# MGT_PWR.net
KiCad netlist of a schematic drawn in Altium Designer
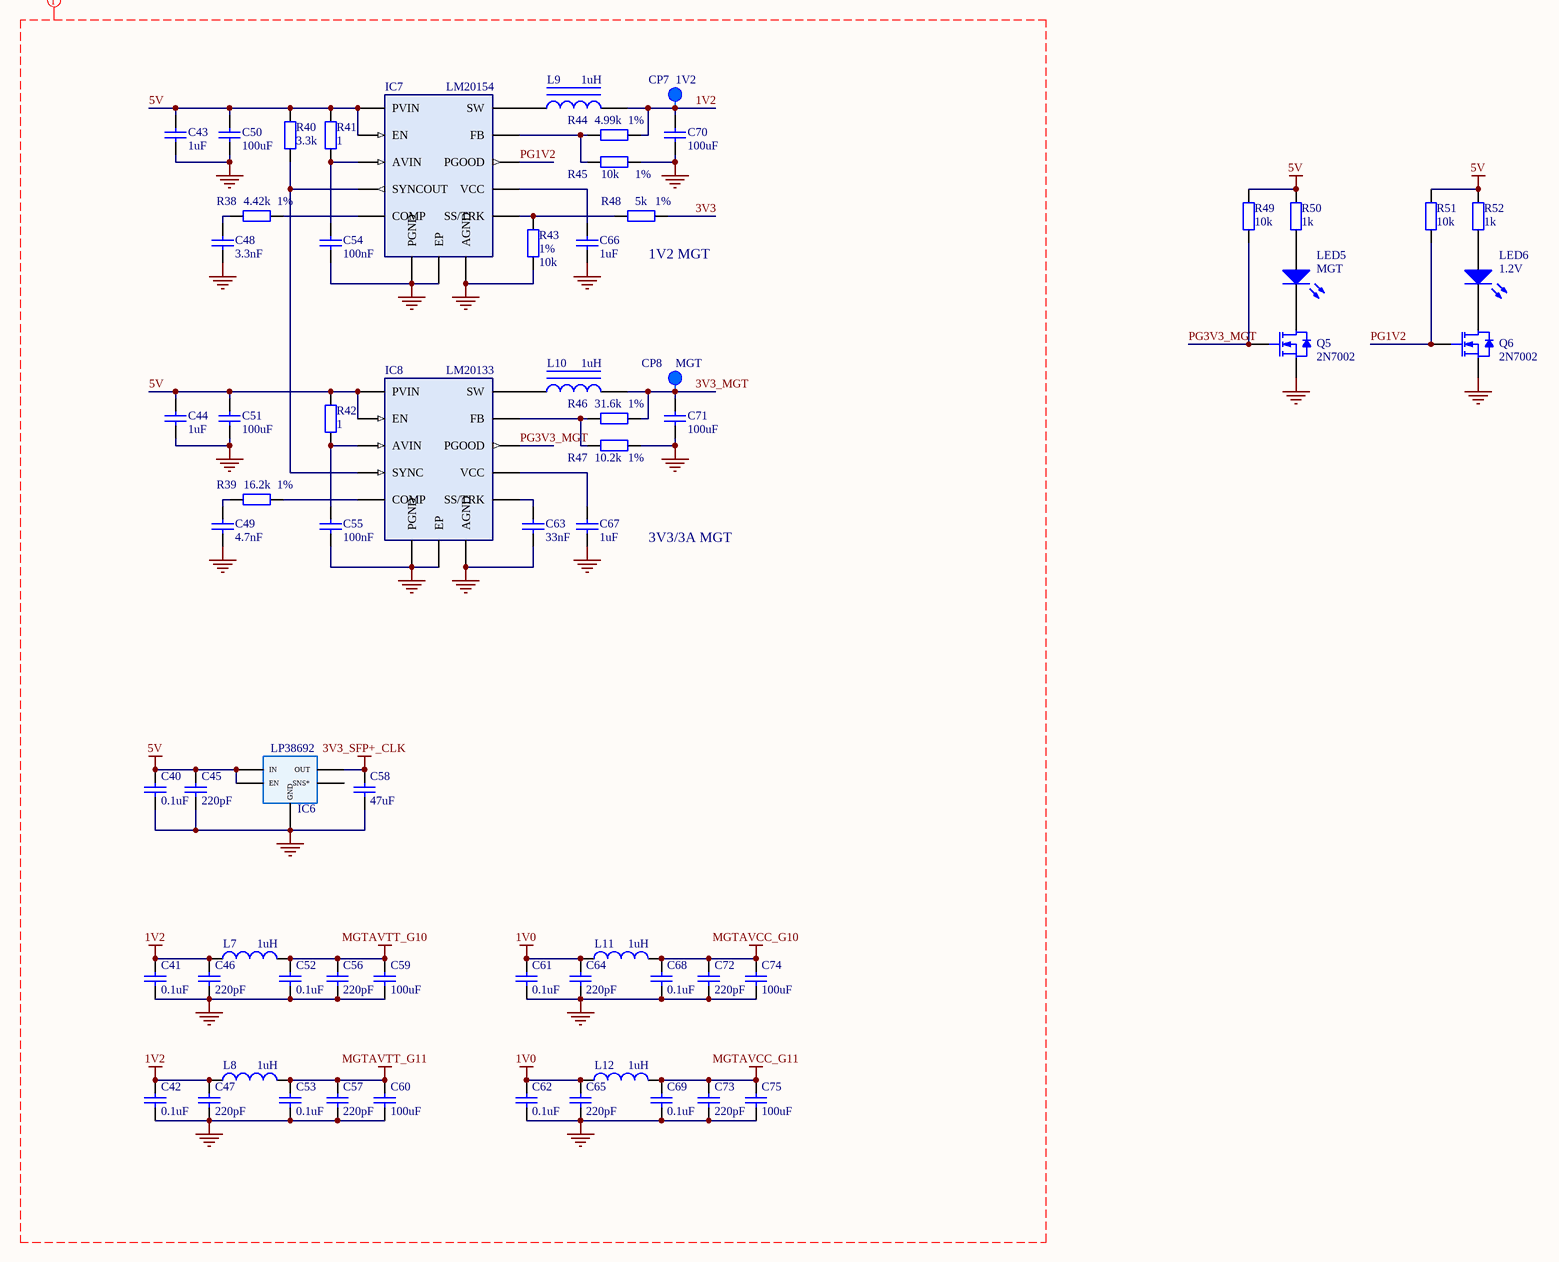
[diagram p0: MGT_PWR.SchDoc]

(export (version "E")
  (design (tool "Eeschema 10.0.6"))
  (components
    (comp (ref "C40")
      (value "0.1uF")
      (footprint "C0603")
      (description "Cer Cap Small")
      (fields (field (name "MANUFACTURER") "Murata") (field (name "VOLTAGE") "16V"))
      (libsource (lib "USRP2_Clone") (part "Cer Cap"))
    )
    (comp (ref "C41")
      (value "0.1uF")
      (footprint "C0603")
      (description "Cer Cap Small")
      (fields (field (name "MANUFACTURER") "Murata") (field (name "VOLTAGE") "16V"))
      (libsource (lib "USRP2_Clone") (part "Cer Cap"))
    )
    (comp (ref "C42")
      (value "0.1uF")
      (footprint "C0603")
      (description "Cer Cap Small")
      (fields (field (name "MANUFACTURER") "Murata") (field (name "VOLTAGE") "16V"))
      (libsource (lib "USRP2_Clone") (part "Cer Cap"))
    )
    (comp (ref "C43")
      (value "1uF")
      (footprint "C0805")
      (description "Cer Cap Small")
      (fields (field (name "MANUFACTURER") "Murata") (field (name "VOLTAGE") "16V"))
      (libsource (lib "USRP2_Clone") (part "Cer Cap"))
    )
    (comp (ref "C44")
      (value "1uF")
      (footprint "C0805")
      (description "Cer Cap Small")
      (fields (field (name "MANUFACTURER") "Murata") (field (name "VOLTAGE") "16V"))
      (libsource (lib "USRP2_Clone") (part "Cer Cap"))
    )
    (comp (ref "C45")
      (value "220pF")
      (footprint "C0603")
      (description "Cer Cap Small")
      (fields (field (name "MANUFACTURER") "Murata") (field (name "VOLTAGE") "16V"))
      (libsource (lib "USRP2_Clone") (part "Cer Cap"))
    )
    (comp (ref "C46")
      (value "220pF")
      (footprint "C0603")
      (description "Cer Cap Small")
      (fields (field (name "MANUFACTURER") "Murata") (field (name "VOLTAGE") "16V"))
      (libsource (lib "USRP2_Clone") (part "Cer Cap"))
    )
    (comp (ref "C47")
      (value "220pF")
      (footprint "C0603")
      (description "Cer Cap Small")
      (fields (field (name "MANUFACTURER") "Murata") (field (name "VOLTAGE") "16V"))
      (libsource (lib "USRP2_Clone") (part "Cer Cap"))
    )
    (comp (ref "C48")
      (value "3.3nF")
      (footprint "C0603")
      (description "Cer Cap Small")
      (fields (field (name "MANUFACTURER") "Murata") (field (name "VOLTAGE") "25V"))
      (libsource (lib "") (part "Cer Cap_1"))
    )
    (comp (ref "C49")
      (value "4.7nF")
      (footprint "C0603")
      (description "Cer Cap Small")
      (fields (field (name "MANUFACTURER") "Murata") (field (name "VOLTAGE") "25V"))
      (libsource (lib "") (part "Cer Cap_1"))
    )
    (comp (ref "C50")
      (value "100uF")
      (footprint "C1210")
      (description "Cer Cap Large")
      (fields (field (name "MANUFACTURER") "Murata") (field (name "TOLERANCE") "20%"))
      (libsource (lib "") (part "Cap uF_1"))
    )
    (comp (ref "C51")
      (value "100uF")
      (footprint "C1210")
      (description "Cer Cap Large")
      (fields (field (name "MANUFACTURER") "Murata") (field (name "TOLERANCE") "20%"))
      (libsource (lib "") (part "Cap uF_1"))
    )
    (comp (ref "C52")
      (value "0.1uF")
      (footprint "C0603")
      (description "Cer Cap Small")
      (fields (field (name "MANUFACTURER") "Murata") (field (name "VOLTAGE") "16V"))
      (libsource (lib "USRP2_Clone") (part "Cer Cap"))
    )
    (comp (ref "C53")
      (value "0.1uF")
      (footprint "C0603")
      (description "Cer Cap Small")
      (fields (field (name "MANUFACTURER") "Murata") (field (name "VOLTAGE") "16V"))
      (libsource (lib "USRP2_Clone") (part "Cer Cap"))
    )
    (comp (ref "C54")
      (value "100nF")
      (footprint "C0603")
      (description "Cer Cap Small")
      (fields (field (name "MANUFACTURER") "Murata") (field (name "VOLTAGE") "16V"))
      (libsource (lib "") (part "Cer Cap_1"))
    )
    (comp (ref "C55")
      (value "100nF")
      (footprint "C0603")
      (description "Cer Cap Small")
      (fields (field (name "MANUFACTURER") "Murata") (field (name "VOLTAGE") "16V"))
      (libsource (lib "") (part "Cer Cap_1"))
    )
    (comp (ref "C56")
      (value "220pF")
      (footprint "C0603")
      (description "Cer Cap Small")
      (fields (field (name "MANUFACTURER") "Murata") (field (name "VOLTAGE") "16V"))
      (libsource (lib "USRP2_Clone") (part "Cer Cap"))
    )
    (comp (ref "C57")
      (value "220pF")
      (footprint "C0603")
      (description "Cer Cap Small")
      (fields (field (name "MANUFACTURER") "Murata") (field (name "VOLTAGE") "16V"))
      (libsource (lib "USRP2_Clone") (part "Cer Cap"))
    )
    (comp (ref "C58")
      (value "47uF")
      (footprint "C1210")
      (description "Cer Cap Large")
      (fields (field (name "MANUFACTURER") "Murata") (field (name "TOLERANCE") "20%"))
      (libsource (lib "") (part "Cap uF_1"))
    )
    (comp (ref "C59")
      (value "100uF")
      (footprint "C1210")
      (description "Cer Cap Large")
      (fields (field (name "MANUFACTURER") "Murata") (field (name "TOLERANCE") "20%"))
      (libsource (lib "") (part "Cap uF_1"))
    )
    (comp (ref "C60")
      (value "100uF")
      (footprint "C1210")
      (description "Cer Cap Large")
      (fields (field (name "MANUFACTURER") "Murata") (field (name "TOLERANCE") "20%"))
      (libsource (lib "") (part "Cap uF_1"))
    )
    (comp (ref "C61")
      (value "0.1uF")
      (footprint "C0603")
      (description "Cer Cap Small")
      (fields (field (name "MANUFACTURER") "Murata") (field (name "VOLTAGE") "16V"))
      (libsource (lib "") (part "Cer Cap_1"))
    )
    (comp (ref "C62")
      (value "0.1uF")
      (footprint "C0603")
      (description "Cer Cap Small")
      (fields (field (name "MANUFACTURER") "Murata") (field (name "VOLTAGE") "16V"))
      (libsource (lib "") (part "Cer Cap_1"))
    )
    (comp (ref "C63")
      (value "33nF")
      (footprint "C0603")
      (description "Cer Cap Small")
      (fields (field (name "MANUFACTURER") "Murata") (field (name "VOLTAGE") "25V"))
      (libsource (lib "USRP2_Clone") (part "Cer Cap"))
    )
    (comp (ref "C64")
      (value "220pF")
      (footprint "C0603")
      (description "Cer Cap Small")
      (fields (field (name "MANUFACTURER") "Murata") (field (name "VOLTAGE") "16V"))
      (libsource (lib "") (part "Cer Cap_1"))
    )
    (comp (ref "C65")
      (value "220pF")
      (footprint "C0603")
      (description "Cer Cap Small")
      (fields (field (name "MANUFACTURER") "Murata") (field (name "VOLTAGE") "16V"))
      (libsource (lib "USRP2_Clone") (part "Cer Cap"))
    )
    (comp (ref "C66")
      (value "1uF")
      (footprint "C0603")
      (description "Cer Cap Small")
      (fields (field (name "MANUFACTURER") "Murata") (field (name "VOLTAGE") "6.3V"))
      (libsource (lib "USRP2_Clone") (part "Cer Cap"))
    )
    (comp (ref "C67")
      (value "1uF")
      (footprint "C0603")
      (description "Cer Cap Small")
      (fields (field (name "MANUFACTURER") "Murata") (field (name "VOLTAGE") "6.3V"))
      (libsource (lib "") (part "Cer Cap_1"))
    )
    (comp (ref "C68")
      (value "0.1uF")
      (footprint "C0603")
      (description "Cer Cap Small")
      (fields (field (name "MANUFACTURER") "Murata") (field (name "VOLTAGE") "16V"))
      (libsource (lib "USRP2_Clone") (part "Cer Cap"))
    )
    (comp (ref "C69")
      (value "0.1uF")
      (footprint "C0603")
      (description "Cer Cap Small")
      (fields (field (name "MANUFACTURER") "Murata") (field (name "VOLTAGE") "16V"))
      (libsource (lib "USRP2_Clone") (part "Cer Cap"))
    )
    (comp (ref "C70")
      (value "100uF")
      (footprint "C1210")
      (description "Cer Cap Large")
      (fields (field (name "MANUFACTURER") "Murata") (field (name "TOLERANCE") "20%"))
      (libsource (lib "USRP2_Clone") (part "Cap uF"))
    )
    (comp (ref "C71")
      (value "100uF")
      (footprint "C1210")
      (description "Cer Cap Large")
      (fields (field (name "MANUFACTURER") "Murata") (field (name "TOLERANCE") "20%"))
      (libsource (lib "USRP2_Clone") (part "Cap uF"))
    )
    (comp (ref "C72")
      (value "220pF")
      (footprint "C0603")
      (description "Cer Cap Small")
      (fields (field (name "MANUFACTURER") "Murata") (field (name "VOLTAGE") "16V"))
      (libsource (lib "USRP2_Clone") (part "Cer Cap"))
    )
    (comp (ref "C73")
      (value "220pF")
      (footprint "C0603")
      (description "Cer Cap Small")
      (fields (field (name "MANUFACTURER") "Murata") (field (name "VOLTAGE") "16V"))
      (libsource (lib "USRP2_Clone") (part "Cer Cap"))
    )
    (comp (ref "C74")
      (value "100uF")
      (footprint "C1210")
      (description "Cer Cap Large")
      (fields (field (name "MANUFACTURER") "Murata") (field (name "TOLERANCE") "20%"))
      (libsource (lib "") (part "Cap uF_1"))
    )
    (comp (ref "C75")
      (value "100uF")
      (footprint "C1210")
      (description "Cer Cap Large")
      (fields (field (name "MANUFACTURER") "Murata") (field (name "TOLERANCE") "20%"))
      (libsource (lib "") (part "Cap uF_1"))
    )
    (comp (ref "CP7")
      (value "1V2")
      (footprint "Control Point")
      (description "Control Point")
      (libsource (lib "USRP2_Clone") (part "Control Point"))
    )
    (comp (ref "CP8")
      (value "MGT")
      (footprint "Control Point")
      (description "Control Point")
      (libsource (lib "USRP2_Clone") (part "Control Point"))
    )
    (comp (ref "IC6")
      (value "LP38692")
      (footprint "SOT-223-5")
      (description "Linear Regulator")
      (libsource (lib "USRP2_Clone") (part "LP38692"))
    )
    (comp (ref "IC7")
      (value "LM20154")
      (footprint "LM201xx")
      (description "Synchrous Buck Regulator")
      (libsource (lib "USRP2_Clone") (part "LM20154"))
    )
    (comp (ref "IC8")
      (value "LM20133")
      (footprint "LM201xx")
      (description "Synchronous Buck Regulator")
      (libsource (lib "USRP2_Clone") (part "LM20133"))
    )
    (comp (ref "L7")
      (value "1uH")
      (footprint "L1210_Murata LQH")
      (description "Inductor_Power_Lines")
      (fields (field (name "TOLERANCE") "5%") (field (name "MANUFACTURER") "Murata"))
      (libsource (lib "USRP2_Clone") (part "Inductor_LF"))
    )
    (comp (ref "L8")
      (value "1uH")
      (footprint "L1210_Murata LQH")
      (description "Inductor_Power_Lines")
      (fields (field (name "TOLERANCE") "5%") (field (name "MANUFACTURER") "Murata"))
      (libsource (lib "USRP2_Clone") (part "Inductor_LF"))
    )
    (comp (ref "L9")
      (value "1uH")
      (footprint "Coilcraft MSS1038")
      (description "Magnetic-Core Inductor")
      (fields (field (name "TOLERANCE") "±30%") (field (name "MANUFACTURER") "Coilcraft"))
      (libsource (lib "USRP2_Clone") (part "Inductor Power"))
    )
    (comp (ref "L10")
      (value "1uH")
      (footprint "Coilcraft MSS1038")
      (description "Magnetic-Core Inductor")
      (fields (field (name "TOLERANCE") "±30%") (field (name "MANUFACTURER") "Coilcraft"))
      (libsource (lib "USRP2_Clone") (part "Inductor Power"))
    )
    (comp (ref "L11")
      (value "1uH")
      (footprint "L1210_Murata LQH")
      (description "Inductor_Power_Lines")
      (fields (field (name "TOLERANCE") "5%") (field (name "MANUFACTURER") "Murata"))
      (libsource (lib "USRP2_Clone") (part "Inductor_LF"))
    )
    (comp (ref "L12")
      (value "1uH")
      (footprint "L1210_Murata LQH")
      (description "Inductor_Power_Lines")
      (fields (field (name "TOLERANCE") "5%") (field (name "MANUFACTURER") "Murata"))
      (libsource (lib "USRP2_Clone") (part "Inductor_LF"))
    )
    (comp (ref "LED5")
      (value "MGT")
      (footprint "LED_0402_Blue")
      (description "Typical RED, GREEN, YELLOW, AMBER GaAs LED")
      (fields (field (name "MANUFACTURER") "Kingbright"))
      (libsource (lib "USRP2_Clone") (part "LED"))
    )
    (comp (ref "LED6")
      (value "1.2V")
      (footprint "LED_0402_Blue")
      (description "Typical RED, GREEN, YELLOW, AMBER GaAs LED")
      (fields (field (name "MANUFACTURER") "Kingbright"))
      (libsource (lib "USRP2_Clone") (part "LED"))
    )
    (comp (ref "Q5")
      (value "2N7002")
      (footprint "SOT-23")
      (description "N-Channel MOSFET 2N7002")
      (fields (field (name "VOLTAGE") "60V"))
      (libsource (lib "USRP2_Clone") (part "2N7002"))
    )
    (comp (ref "Q6")
      (value "2N7002")
      (footprint "SOT-23")
      (description "N-Channel MOSFET 2N7002")
      (fields (field (name "VOLTAGE") "60V"))
      (libsource (lib "USRP2_Clone") (part "2N7002"))
    )
    (comp (ref "R38")
      (value "4.42k")
      (footprint "R0603")
      (description "Resistor")
      (fields
        (field (name "TOLERANCE") "1%")
        (field (name "POWER") "0.062 Wt")
        (field (name "Comment") "Res")
      )
      (libsource (lib "") (part "Res_3"))
    )
    (comp (ref "R39")
      (value "16.2k")
      (footprint "R0603")
      (description "Resistor")
      (fields
        (field (name "TOLERANCE") "1%")
        (field (name "POWER") "0.062 Wt")
        (field (name "Comment") "Res")
      )
      (libsource (lib "") (part "Res_2"))
    )
    (comp (ref "R40")
      (value "3.3k")
      (footprint "R0603")
      (description "Resistor")
      (fields (field (name "TOLERANCE") "5%") (field (name "POWER") "0.062 Wt"))
      (libsource (lib "") (part "Res_1"))
    )
    (comp (ref "R41")
      (value "1")
      (footprint "R0603")
      (description "Resistor")
      (fields (field (name "TOLERANCE") "5%") (field (name "POWER") "0.062 Wt"))
      (libsource (lib "") (part "Res_5"))
    )
    (comp (ref "R42")
      (value "1")
      (footprint "R0603")
      (description "Resistor")
      (fields (field (name "TOLERANCE") "5%") (field (name "POWER") "0.062 Wt"))
      (libsource (lib "USRP2_Clone") (part "Res"))
    )
    (comp (ref "R43")
      (value "10k")
      (footprint "R0603")
      (description "Resistor")
      (fields
        (field (name "TOLERANCE") "1%")
        (field (name "POWER") "0.062 Wt")
        (field (name "Comment") "Res")
      )
      (libsource (lib "") (part "Res_4"))
    )
    (comp (ref "R44")
      (value "4.99k")
      (footprint "R0603")
      (description "Resistor")
      (fields
        (field (name "TOLERANCE") "1%")
        (field (name "POWER") "0.062 Wt")
        (field (name "Comment") "Res")
      )
      (libsource (lib "") (part "Res_2"))
    )
    (comp (ref "R45")
      (value "10k")
      (footprint "R0603")
      (description "Resistor")
      (fields
        (field (name "TOLERANCE") "1%")
        (field (name "POWER") "0.062 Wt")
        (field (name "Comment") "Res")
      )
      (libsource (lib "") (part "Res_3"))
    )
    (comp (ref "R46")
      (value "31.6k")
      (footprint "R0603")
      (description "Resistor")
      (fields
        (field (name "TOLERANCE") "1%")
        (field (name "POWER") "0.062 Wt")
        (field (name "Comment") "Res")
      )
      (libsource (lib "") (part "Res_2"))
    )
    (comp (ref "R47")
      (value "10.2k")
      (footprint "R0603")
      (description "Resistor")
      (fields
        (field (name "TOLERANCE") "1%")
        (field (name "POWER") "0.062 Wt")
        (field (name "Comment") "Res")
      )
      (libsource (lib "") (part "Res_3"))
    )
    (comp (ref "R48")
      (value "5k")
      (footprint "R0603")
      (description "Resistor")
      (fields
        (field (name "TOLERANCE") "1%")
        (field (name "POWER") "0.062 Wt")
        (field (name "Comment") "Res")
      )
      (libsource (lib "") (part "Res_2"))
    )
    (comp (ref "R49")
      (value "10k")
      (footprint "R0402")
      (description "Resistor")
      (fields (field (name "TOLERANCE") "5%") (field (name "POWER") "0.062 Wt"))
      (libsource (lib "USRP2_Clone") (part "Res"))
    )
    (comp (ref "R50")
      (value "1k")
      (footprint "R0402")
      (description "Resistor")
      (fields (field (name "TOLERANCE") "5%") (field (name "POWER") "0.062 Wt"))
      (libsource (lib "USRP2_Clone") (part "Res"))
    )
    (comp (ref "R51")
      (value "10k")
      (footprint "R0402")
      (description "Resistor")
      (fields (field (name "TOLERANCE") "5%") (field (name "POWER") "0.062 Wt"))
      (libsource (lib "USRP2_Clone") (part "Res"))
    )
    (comp (ref "R52")
      (value "1k")
      (footprint "R0402")
      (description "Resistor")
      (fields (field (name "TOLERANCE") "5%") (field (name "POWER") "0.062 Wt"))
      (libsource (lib "USRP2_Clone") (part "Res"))
    )
  )
  (nets
    (net (code "1") (name "/3V3") (class "Default")
      (node (ref "R48") (pin "1") (pinfunction "1_1") (pintype "passive"))
    )
    (net (code "2") (name "/3V3_MGT") (class "Default")
      (node (ref "C71") (pin "2") (pinfunction "2_2") (pintype "passive"))
      (node (ref "CP8") (pin "1") (pinfunction "1_1") (pintype "passive"))
      (node (ref "L10") (pin "2") (pinfunction "2_2") (pintype "passive"))
      (node (ref "R46") (pin "1") (pinfunction "1_1") (pintype "passive"))
    )
    (net (code "3") (name "/PG1V2") (class "Default")
      (node (ref "IC7") (pin "3") (pinfunction "PGOOD_3") (pintype "output"))
      (node (ref "Q6") (pin "1") (pinfunction "G_1") (pintype "passive"))
      (node (ref "R51") (pin "1") (pinfunction "1_1") (pintype "passive"))
    )
    (net (code "4") (name "/PG3V3_MGT") (class "Default")
      (node (ref "IC8") (pin "3") (pinfunction "PGOOD_3") (pintype "output"))
      (node (ref "Q5") (pin "1") (pinfunction "G_1") (pintype "passive"))
      (node (ref "R49") (pin "1") (pinfunction "1_1") (pintype "passive"))
    )
    (net (code "5") (name "1V0") (class "Default")
      (node (ref "C61") (pin "2") (pinfunction "2_2") (pintype "passive"))
      (node (ref "C62") (pin "2") (pinfunction "2_2") (pintype "passive"))
      (node (ref "C64") (pin "2") (pinfunction "2_2") (pintype "passive"))
      (node (ref "C65") (pin "1") (pinfunction "1_1") (pintype "passive"))
      (node (ref "L11") (pin "2") (pinfunction "2_2") (pintype "passive"))
      (node (ref "L12") (pin "2") (pinfunction "2_2") (pintype "passive"))
    )
    (net (code "6") (name "1V2") (class "Default")
      (node (ref "C41") (pin "1") (pinfunction "1_1") (pintype "passive"))
      (node (ref "C42") (pin "1") (pinfunction "1_1") (pintype "passive"))
      (node (ref "C46") (pin "1") (pinfunction "1_1") (pintype "passive"))
      (node (ref "C47") (pin "1") (pinfunction "1_1") (pintype "passive"))
      (node (ref "C70") (pin "2") (pinfunction "2_2") (pintype "passive"))
      (node (ref "CP7") (pin "1") (pinfunction "1_1") (pintype "passive"))
      (node (ref "L7") (pin "2") (pinfunction "2_2") (pintype "passive"))
      (node (ref "L8") (pin "2") (pinfunction "2_2") (pintype "passive"))
      (node (ref "L9") (pin "2") (pinfunction "2_2") (pintype "passive"))
      (node (ref "R44") (pin "1") (pinfunction "1_1") (pintype "passive"))
    )
    (net (code "7") (name "3V3_SFP+_CLK") (class "Default")
      (node (ref "C58") (pin "1") (pinfunction "1_1") (pintype "passive"))
      (node (ref "IC6") (pin "3") (pinfunction "OUT_3") (pintype "passive"))
    )
    (net (code "8") (name "5V") (class "Default")
      (node (ref "C40") (pin "1") (pinfunction "1_1") (pintype "passive"))
      (node (ref "C43") (pin "1") (pinfunction "1_1") (pintype "passive"))
      (node (ref "C44") (pin "1") (pinfunction "1_1") (pintype "passive"))
      (node (ref "C45") (pin "1") (pinfunction "1_1") (pintype "passive"))
      (node (ref "C50") (pin "1") (pinfunction "1_1") (pintype "passive"))
      (node (ref "C51") (pin "1") (pinfunction "1_1") (pintype "passive"))
      (node (ref "IC6") (pin "1") (pinfunction "EN_1") (pintype "passive"))
      (node (ref "IC6") (pin "4") (pinfunction "IN_4") (pintype "passive"))
      (node (ref "IC7") (pin "12") (pinfunction "EN_12") (pintype "input"))
      (node (ref "IC7") (pin "6") (pinfunction "PVIN_6") (pintype "passive"))
      (node (ref "IC8") (pin "12") (pinfunction "EN_12") (pintype "input"))
      (node (ref "IC8") (pin "6") (pinfunction "PVIN_6") (pintype "passive"))
      (node (ref "R40") (pin "2") (pinfunction "2_2") (pintype "passive"))
      (node (ref "R41") (pin "1") (pinfunction "1_1") (pintype "passive"))
      (node (ref "R42") (pin "2") (pinfunction "2_2") (pintype "passive"))
      (node (ref "R49") (pin "2") (pinfunction "2_2") (pintype "passive"))
      (node (ref "R50") (pin "2") (pinfunction "2_2") (pintype "passive"))
      (node (ref "R51") (pin "2") (pinfunction "2_2") (pintype "passive"))
      (node (ref "R52") (pin "2") (pinfunction "2_2") (pintype "passive"))
    )
    (net (code "9") (name "GND") (class "Default")
      (node (ref "C40") (pin "2") (pinfunction "2_2") (pintype "passive"))
      (node (ref "C41") (pin "2") (pinfunction "2_2") (pintype "passive"))
      (node (ref "C42") (pin "2") (pinfunction "2_2") (pintype "passive"))
      (node (ref "C43") (pin "2") (pinfunction "2_2") (pintype "passive"))
      (node (ref "C44") (pin "2") (pinfunction "2_2") (pintype "passive"))
      (node (ref "C45") (pin "2") (pinfunction "2_2") (pintype "passive"))
      (node (ref "C46") (pin "2") (pinfunction "2_2") (pintype "passive"))
      (node (ref "C47") (pin "2") (pinfunction "2_2") (pintype "passive"))
      (node (ref "C48") (pin "1") (pinfunction "1_1") (pintype "passive"))
      (node (ref "C49") (pin "1") (pinfunction "1_1") (pintype "passive"))
      (node (ref "C50") (pin "2") (pinfunction "2_2") (pintype "passive"))
      (node (ref "C51") (pin "2") (pinfunction "2_2") (pintype "passive"))
      (node (ref "C52") (pin "2") (pinfunction "2_2") (pintype "passive"))
      (node (ref "C53") (pin "2") (pinfunction "2_2") (pintype "passive"))
      (node (ref "C54") (pin "2") (pinfunction "2_2") (pintype "passive"))
      (node (ref "C55") (pin "2") (pinfunction "2_2") (pintype "passive"))
      (node (ref "C56") (pin "2") (pinfunction "2_2") (pintype "passive"))
      (node (ref "C57") (pin "2") (pinfunction "2_2") (pintype "passive"))
      (node (ref "C58") (pin "2") (pinfunction "2_2") (pintype "passive"))
      (node (ref "C59") (pin "2") (pinfunction "2_2") (pintype "passive"))
      (node (ref "C60") (pin "2") (pinfunction "2_2") (pintype "passive"))
      (node (ref "C61") (pin "1") (pinfunction "1_1") (pintype "passive"))
      (node (ref "C62") (pin "1") (pinfunction "1_1") (pintype "passive"))
      (node (ref "C63") (pin "2") (pinfunction "2_2") (pintype "passive"))
      (node (ref "C64") (pin "1") (pinfunction "1_1") (pintype "passive"))
      (node (ref "C65") (pin "2") (pinfunction "2_2") (pintype "passive"))
      (node (ref "C66") (pin "2") (pinfunction "2_2") (pintype "passive"))
      (node (ref "C67") (pin "1") (pinfunction "1_1") (pintype "passive"))
      (node (ref "C68") (pin "2") (pinfunction "2_2") (pintype "passive"))
      (node (ref "C69") (pin "2") (pinfunction "2_2") (pintype "passive"))
      (node (ref "C70") (pin "1") (pinfunction "1_1") (pintype "passive"))
      (node (ref "C71") (pin "1") (pinfunction "1_1") (pintype "passive"))
      (node (ref "C72") (pin "2") (pinfunction "2_2") (pintype "passive"))
      (node (ref "C73") (pin "2") (pinfunction "2_2") (pintype "passive"))
      (node (ref "C74") (pin "2") (pinfunction "2_2") (pintype "passive"))
      (node (ref "C75") (pin "2") (pinfunction "2_2") (pintype "passive"))
      (node (ref "IC6") (pin "5") (pinfunction "GND_5") (pintype "passive"))
      (node (ref "IC7") (pin "10") (pinfunction "PGND_10") (pintype "passive"))
      (node (ref "IC7") (pin "15") (pinfunction "AGND_15") (pintype "passive"))
      (node (ref "IC7") (pin "17") (pinfunction "EP_17") (pintype "passive"))
      (node (ref "IC8") (pin "10") (pinfunction "PGND_10") (pintype "passive"))
      (node (ref "IC8") (pin "15") (pinfunction "AGND_15") (pintype "passive"))
      (node (ref "IC8") (pin "17") (pinfunction "EP_17") (pintype "passive"))
      (node (ref "Q5") (pin "2") (pinfunction "S_2") (pintype "passive"))
      (node (ref "Q6") (pin "2") (pinfunction "S_2") (pintype "passive"))
      (node (ref "R43") (pin "2") (pinfunction "2_2") (pintype "passive"))
      (node (ref "R45") (pin "2") (pinfunction "2_2") (pintype "passive"))
      (node (ref "R47") (pin "2") (pinfunction "2_2") (pintype "passive"))
    )
    (net (code "10") (name "MGTAVCC_G10") (class "Default")
      (node (ref "C68") (pin "1") (pinfunction "1_1") (pintype "passive"))
      (node (ref "C72") (pin "1") (pinfunction "1_1") (pintype "passive"))
      (node (ref "C74") (pin "1") (pinfunction "1_1") (pintype "passive"))
      (node (ref "L11") (pin "1") (pinfunction "1_1") (pintype "passive"))
    )
    (net (code "11") (name "MGTAVCC_G11") (class "Default")
      (node (ref "C69") (pin "1") (pinfunction "1_1") (pintype "passive"))
      (node (ref "C73") (pin "1") (pinfunction "1_1") (pintype "passive"))
      (node (ref "C75") (pin "1") (pinfunction "1_1") (pintype "passive"))
      (node (ref "L12") (pin "1") (pinfunction "1_1") (pintype "passive"))
    )
    (net (code "12") (name "MGTAVTT_G10") (class "Default")
      (node (ref "C52") (pin "1") (pinfunction "1_1") (pintype "passive"))
      (node (ref "C56") (pin "1") (pinfunction "1_1") (pintype "passive"))
      (node (ref "C59") (pin "1") (pinfunction "1_1") (pintype "passive"))
      (node (ref "L7") (pin "1") (pinfunction "1_1") (pintype "passive"))
    )
    (net (code "13") (name "MGTAVTT_G11") (class "Default")
      (node (ref "C53") (pin "1") (pinfunction "1_1") (pintype "passive"))
      (node (ref "C57") (pin "1") (pinfunction "1_1") (pintype "passive"))
      (node (ref "C60") (pin "1") (pinfunction "1_1") (pintype "passive"))
      (node (ref "L8") (pin "1") (pinfunction "1_1") (pintype "passive"))
    )
    (net (code "14") (name "Net-(C48-Pad2)") (class "Default")
      (node (ref "C48") (pin "2") (pinfunction "2_2") (pintype "passive"))
      (node (ref "R38") (pin "1") (pinfunction "1_1") (pintype "passive"))
    )
    (net (code "15") (name "Net-(C49-Pad2)") (class "Default")
      (node (ref "C49") (pin "2") (pinfunction "2_2") (pintype "passive"))
      (node (ref "R39") (pin "2") (pinfunction "2_2") (pintype "passive"))
    )
    (net (code "16") (name "Net-(IC7-AVIN)") (class "Default")
      (node (ref "C54") (pin "1") (pinfunction "1_1") (pintype "passive"))
      (node (ref "IC7") (pin "14") (pinfunction "AVIN_14") (pintype "input"))
      (node (ref "R41") (pin "2") (pinfunction "2_2") (pintype "passive"))
    )
    (net (code "17") (name "Net-(IC7-COMP)") (class "Default")
      (node (ref "IC7") (pin "4") (pinfunction "COMP_4") (pintype "passive"))
      (node (ref "R38") (pin "2") (pinfunction "2_2") (pintype "passive"))
    )
    (net (code "18") (name "Net-(IC7-FB)") (class "Default")
      (node (ref "IC7") (pin "2") (pinfunction "FB_2") (pintype "passive"))
      (node (ref "R44") (pin "2") (pinfunction "2_2") (pintype "passive"))
      (node (ref "R45") (pin "1") (pinfunction "1_1") (pintype "passive"))
    )
    (net (code "19") (name "Net-(IC7-SS{slash}TRK)") (class "Default")
      (node (ref "IC7") (pin "1") (pinfunction "SS/TRK_1") (pintype "passive"))
      (node (ref "R43") (pin "1") (pinfunction "1_1") (pintype "passive"))
      (node (ref "R48") (pin "2") (pinfunction "2_2") (pintype "passive"))
    )
    (net (code "20") (name "Net-(IC7-SW)") (class "Default")
      (node (ref "IC7") (pin "8") (pinfunction "SW_8") (pintype "passive"))
      (node (ref "L9") (pin "1") (pinfunction "1_1") (pintype "passive"))
    )
    (net (code "21") (name "Net-(IC7-SYNCOUT)") (class "Default")
      (node (ref "IC7") (pin "16") (pinfunction "SYNCOUT_16") (pintype "output"))
      (node (ref "IC8") (pin "16") (pinfunction "SYNC_16") (pintype "input"))
      (node (ref "R40") (pin "1") (pinfunction "1_1") (pintype "passive"))
    )
    (net (code "22") (name "Net-(IC7-VCC)") (class "Default")
      (node (ref "C66") (pin "1") (pinfunction "1_1") (pintype "passive"))
      (node (ref "IC7") (pin "13") (pinfunction "VCC_13") (pintype "passive"))
    )
    (net (code "23") (name "Net-(IC8-AVIN)") (class "Default")
      (node (ref "C55") (pin "1") (pinfunction "1_1") (pintype "passive"))
      (node (ref "IC8") (pin "14") (pinfunction "AVIN_14") (pintype "input"))
      (node (ref "R42") (pin "1") (pinfunction "1_1") (pintype "passive"))
    )
    (net (code "24") (name "Net-(IC8-COMP)") (class "Default")
      (node (ref "IC8") (pin "4") (pinfunction "COMP_4") (pintype "passive"))
      (node (ref "R39") (pin "1") (pinfunction "1_1") (pintype "passive"))
    )
    (net (code "25") (name "Net-(IC8-FB)") (class "Default")
      (node (ref "IC8") (pin "2") (pinfunction "FB_2") (pintype "passive"))
      (node (ref "R46") (pin "2") (pinfunction "2_2") (pintype "passive"))
      (node (ref "R47") (pin "1") (pinfunction "1_1") (pintype "passive"))
    )
    (net (code "26") (name "Net-(IC8-SS{slash}TRK)") (class "Default")
      (node (ref "C63") (pin "1") (pinfunction "1_1") (pintype "passive"))
      (node (ref "IC8") (pin "1") (pinfunction "SS/TRK_1") (pintype "passive"))
    )
    (net (code "27") (name "Net-(IC8-SW)") (class "Default")
      (node (ref "IC8") (pin "8") (pinfunction "SW_8") (pintype "passive"))
      (node (ref "L10") (pin "1") (pinfunction "1_1") (pintype "passive"))
    )
    (net (code "28") (name "Net-(IC8-VCC)") (class "Default")
      (node (ref "C67") (pin "2") (pinfunction "2_2") (pintype "passive"))
      (node (ref "IC8") (pin "13") (pinfunction "VCC_13") (pintype "passive"))
    )
    (net (code "29") (name "Net-(LED5-A)") (class "Default")
      (node (ref "LED5") (pin "2") (pinfunction "A_2") (pintype "passive"))
      (node (ref "R50") (pin "1") (pinfunction "1_1") (pintype "passive"))
    )
    (net (code "30") (name "Net-(LED5-K)") (class "Default")
      (node (ref "LED5") (pin "1") (pinfunction "K_1") (pintype "passive"))
      (node (ref "Q5") (pin "3") (pinfunction "D_3") (pintype "passive"))
    )
    (net (code "31") (name "Net-(LED6-A)") (class "Default")
      (node (ref "LED6") (pin "2") (pinfunction "A_2") (pintype "passive"))
      (node (ref "R52") (pin "1") (pinfunction "1_1") (pintype "passive"))
    )
    (net (code "32") (name "Net-(LED6-K)") (class "Default")
      (node (ref "LED6") (pin "1") (pinfunction "K_1") (pintype "passive"))
      (node (ref "Q6") (pin "3") (pinfunction "D_3") (pintype "passive"))
    )
    (net (code "33") (name "unconnected-(IC6-SNS*-Pad6)") (class "Default")
      (node (ref "IC6") (pin "6") (pinfunction "SNS*_6") (pintype "passive"))
    )
  )
)
